# TJMakes_LiPo_Manager.net
KiCad netlist of a schematic drawn in EasyEDA Pro
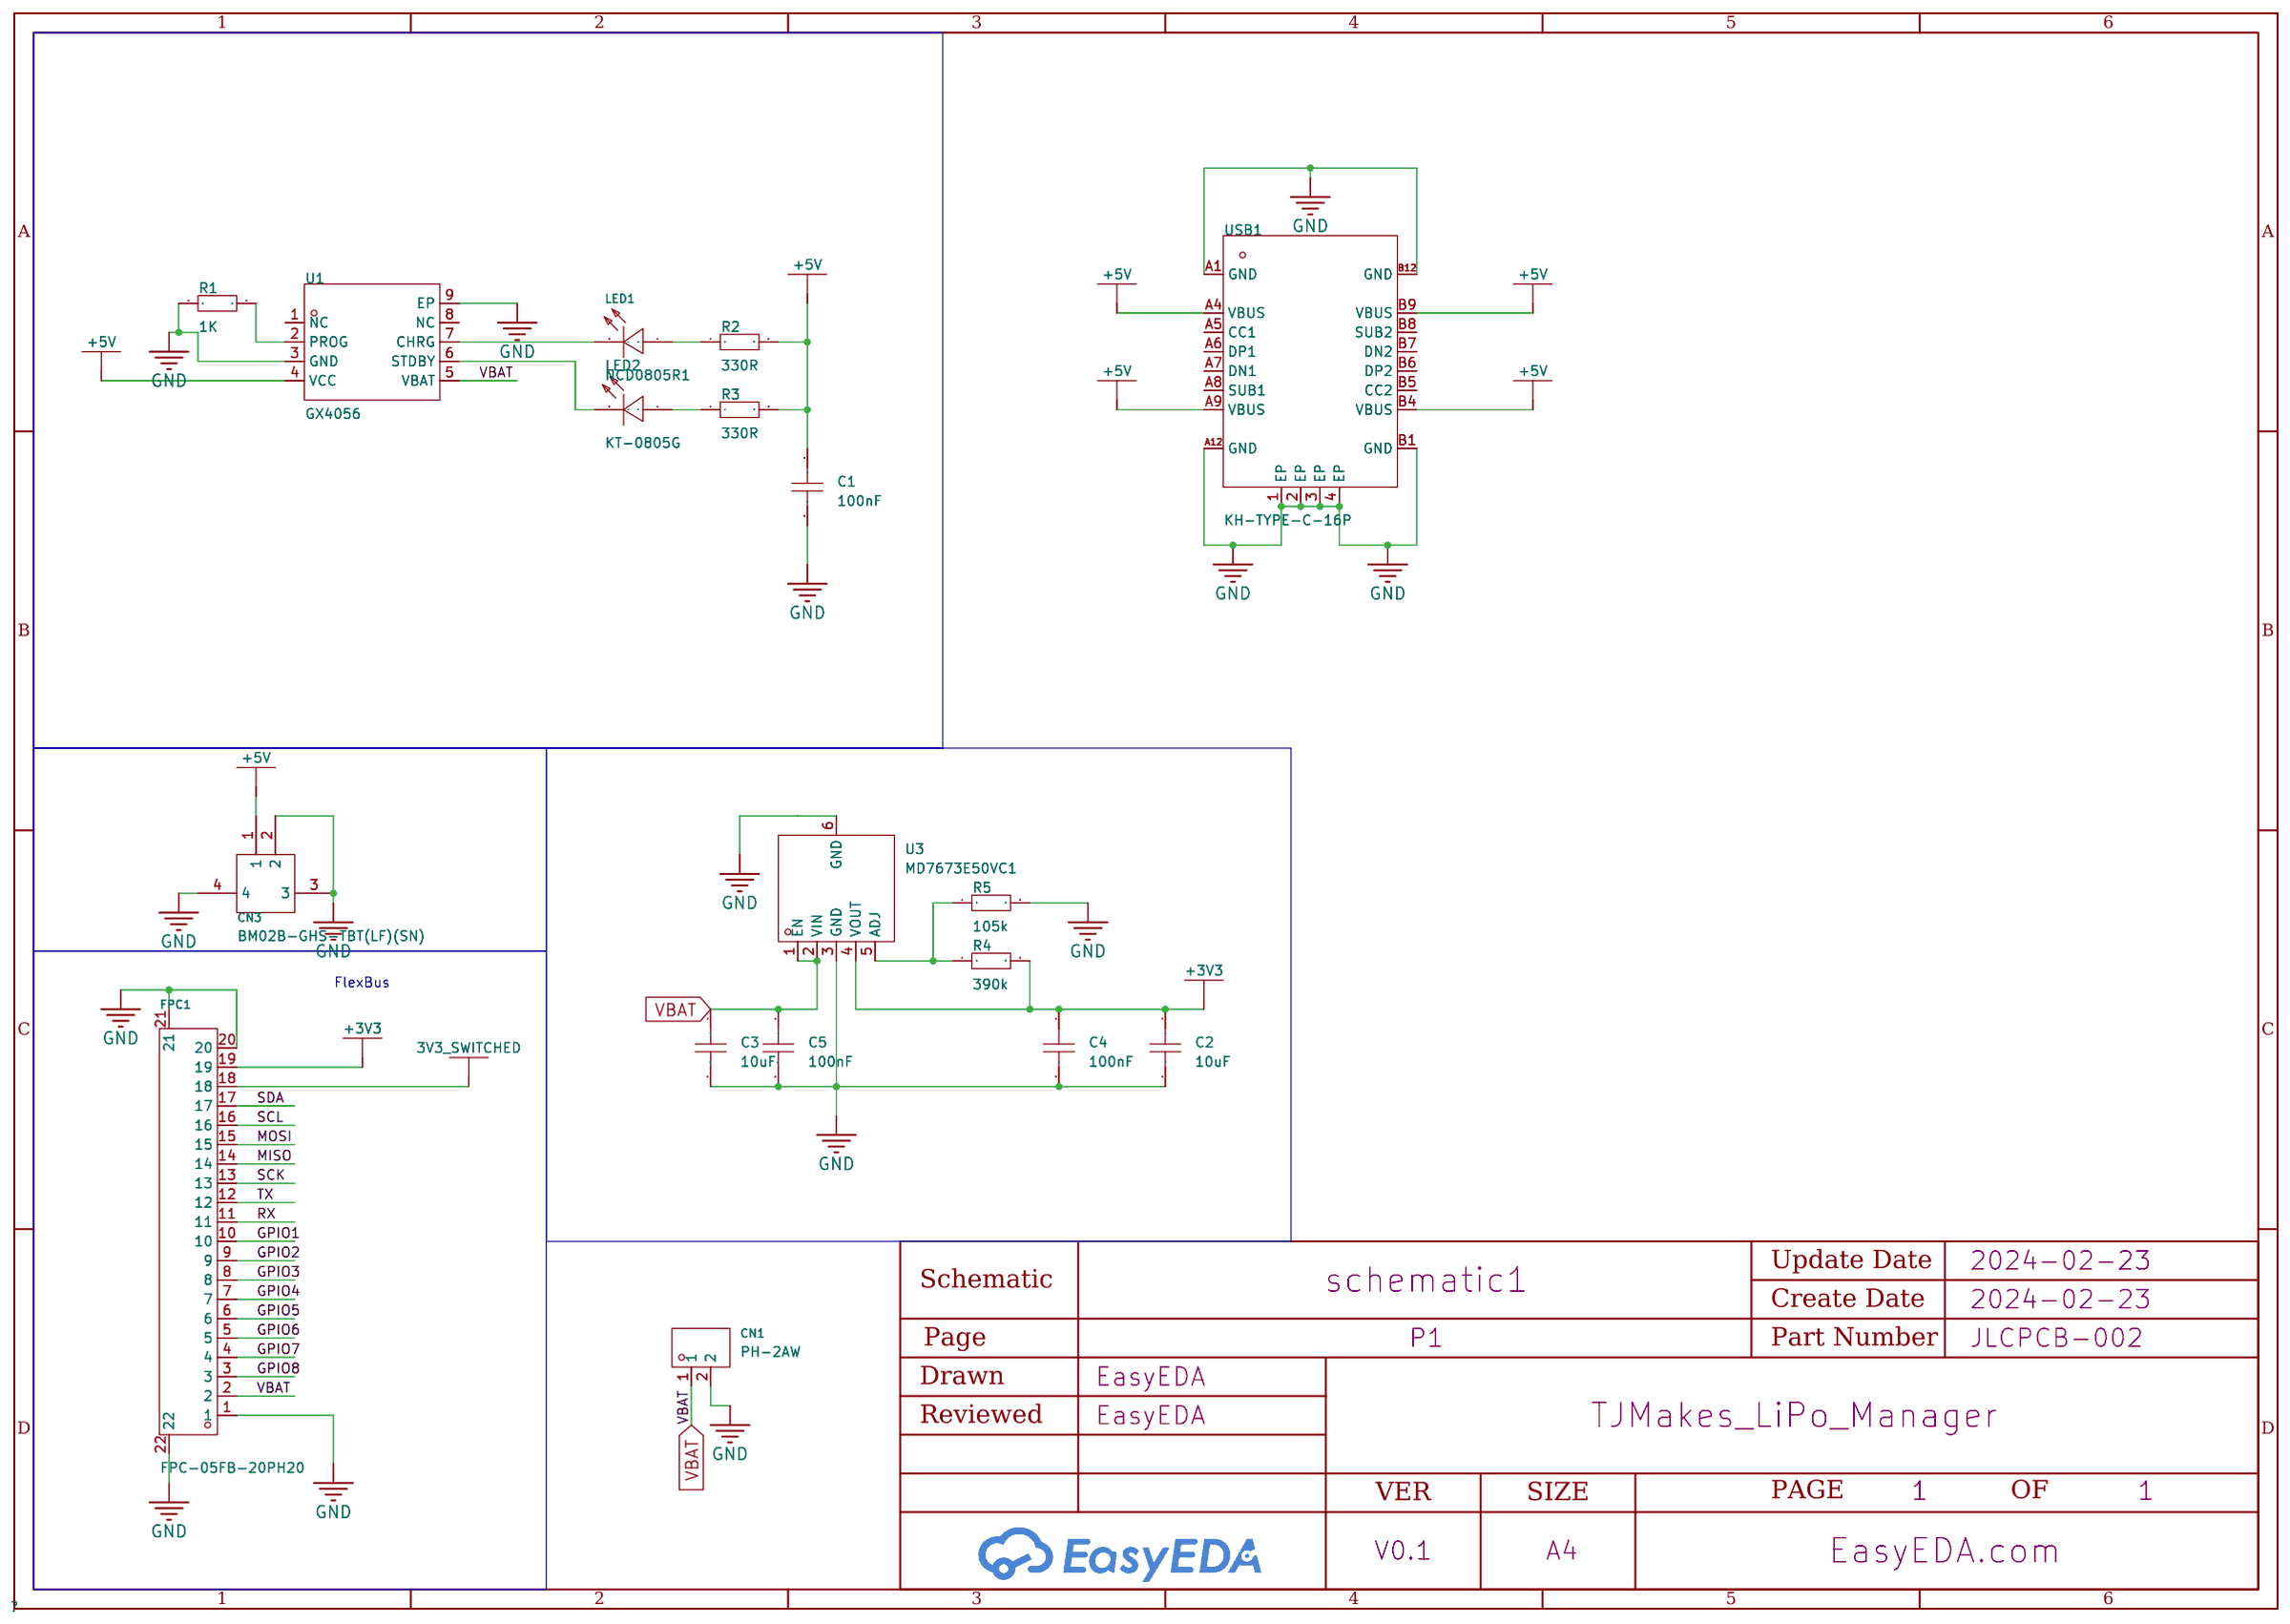
[diagram p0: schematic sheet]

(export (version "E")
  (design (tool "Eeschema 10.0.6"))
  (components
    (comp (ref "C1")
      (value "100nF")
      (footprint "easyedapro:C0603")
      (libsource (lib "easyedapro") (part "CAP"))
    )
    (comp (ref "C2")
      (value "10uF")
      (footprint "easyedapro:C0603")
      (libsource (lib "easyedapro") (part "CAP"))
    )
    (comp (ref "C3")
      (value "10uF")
      (footprint "easyedapro:C0603")
      (libsource (lib "easyedapro") (part "CAP"))
    )
    (comp (ref "C4")
      (value "100nF")
      (footprint "easyedapro:C0603")
      (libsource (lib "easyedapro") (part "CAP"))
    )
    (comp (ref "C5")
      (value "100nF")
      (footprint "easyedapro:C0603")
      (libsource (lib "easyedapro") (part "CAP"))
    )
    (comp (ref "CN1")
      (value "PH-2AW")
      (footprint "easyedapro:CONN-TH_PH-2AW")
      (fields (field (name "Manufacturer") "CAX(创都)"))
      (libsource (lib "easyedapro") (part "PH-2AW"))
    )
    (comp (ref "CN3")
      (value "BM02B-GHS-TBT(LF)(SN)")
      (footprint "easyedapro:CONN-SMD_2P-P1.25_BM02B-GHS-TBT-LF-SN")
      (fields (field (name "Manufacturer") "JST"))
      (libsource (lib "easyedapro") (part "BM02B-GHS-TBT (LF)(SN)"))
    )
    (comp (ref "FPC1")
      (value "FPC-05FB-20PH20")
      (footprint "easyedapro:FPC-SMD_20P-P0.50_FPC-05FB-20PH20")
      (fields (field (name "Manufacturer") "XUNPU(讯普)"))
      (libsource (lib "easyedapro") (part "FPC-05FB-20PH20"))
    )
    (comp (ref "LED1")
      (value "NCD0805R1")
      (footprint "easyedapro:LED0805-R-RD")
      (fields (field (name "Manufacturer") "国星光电"))
      (libsource (lib "easyedapro") (part "FC-2012HRK-620D"))
    )
    (comp (ref "LED2")
      (value "KT-0805G")
      (footprint "easyedapro:LED0805-R-RD")
      (fields (field (name "Manufacturer") "KENTO"))
      (libsource (lib "easyedapro") (part "0805G (Green)"))
    )
    (comp (ref "R1") (value "1K") (footprint "easyedapro:R0603") (libsource (lib "easyedapro") (part "Res")))
    (comp (ref "R2")
      (value "330R")
      (footprint "easyedapro:R0603")
      (libsource (lib "easyedapro") (part "Res"))
    )
    (comp (ref "R3")
      (value "330R")
      (footprint "easyedapro:R0603")
      (libsource (lib "easyedapro") (part "Res"))
    )
    (comp (ref "R4")
      (value "390k")
      (footprint "easyedapro:R0603")
      (libsource (lib "easyedapro") (part "Res"))
    )
    (comp (ref "R5")
      (value "105k")
      (footprint "easyedapro:R0603")
      (libsource (lib "easyedapro") (part "Res"))
    )
    (comp (ref "U1")
      (value "GX4056")
      (footprint "easyedapro:ESOP-8_L4.9-W3.9-P1.27-LS6.0-BL-EP")
      (description "Maximum Charge Current:1000mA")
      (fields (field (name "Manufacturer") "国芯佳品"))
      (libsource (lib "easyedapro") (part "GX4056"))
    )
    (comp (ref "U3")
      (value "MD7673E50VC1")
      (footprint "easyedapro:TO-263-5_L10.2-W8.9-P1.70-BR")
      (fields (field (name "Manufacturer") "明达微"))
      (libsource (lib "easyedapro") (part "MD7673E50VC1"))
    )
    (comp (ref "USB1")
      (value "KH-TYPE-C-16P")
      (footprint "easyedapro:USB-C-SMD_KH-TYPE-C-16P")
      (fields (field (name "Manufacturer") "kinghelm(金航标)"))
      (libsource (lib "easyedapro") (part "KH-TYPE-C-16P"))
    )
  )
  (nets
    (net (code "1") (name "+3V3") (class "Default")
      (node (ref "C2") (pin "1") (pinfunction "1_1") (pintype "input"))
      (node (ref "C4") (pin "1") (pinfunction "1_1") (pintype "input"))
      (node (ref "FPC1") (pin "19") (pinfunction "19_19") (pintype "input"))
      (node (ref "R4") (pin "2") (pinfunction "2_2") (pintype "input"))
      (node (ref "U3") (pin "4") (pinfunction "VOUT_4") (pintype "input"))
    )
    (net (code "2") (name "+5V") (class "Default")
      (node (ref "C1") (pin "1") (pinfunction "1_1") (pintype "input"))
      (node (ref "CN3") (pin "1") (pinfunction "1_1") (pintype "input"))
      (node (ref "R2") (pin "2") (pinfunction "2_2") (pintype "input"))
      (node (ref "R3") (pin "2") (pinfunction "2_2") (pintype "input"))
      (node (ref "U1") (pin "4") (pinfunction "VCC_4") (pintype "input"))
      (node (ref "USB1") (pin "A4") (pinfunction "VBUS_A4") (pintype "unspecified"))
      (node (ref "USB1") (pin "A9") (pinfunction "VBUS_A9") (pintype "unspecified"))
      (node (ref "USB1") (pin "B4") (pinfunction "VBUS_B4") (pintype "unspecified"))
      (node (ref "USB1") (pin "B9") (pinfunction "VBUS_B9") (pintype "unspecified"))
    )
    (net (code "3") (name "/GPIO1") (class "Default")
      (node (ref "FPC1") (pin "10") (pinfunction "10_10") (pintype "input"))
    )
    (net (code "4") (name "/GPIO2") (class "Default")
      (node (ref "FPC1") (pin "9") (pinfunction "9_9") (pintype "input"))
    )
    (net (code "5") (name "/GPIO3") (class "Default")
      (node (ref "FPC1") (pin "8") (pinfunction "8_8") (pintype "input"))
    )
    (net (code "6") (name "/GPIO4") (class "Default")
      (node (ref "FPC1") (pin "7") (pinfunction "7_7") (pintype "input"))
    )
    (net (code "7") (name "/GPIO5") (class "Default")
      (node (ref "FPC1") (pin "6") (pinfunction "6_6") (pintype "input"))
    )
    (net (code "8") (name "/GPIO6") (class "Default")
      (node (ref "FPC1") (pin "5") (pinfunction "5_5") (pintype "input"))
    )
    (net (code "9") (name "/GPIO7") (class "Default")
      (node (ref "FPC1") (pin "4") (pinfunction "4_4") (pintype "input"))
    )
    (net (code "10") (name "/GPIO8") (class "Default")
      (node (ref "FPC1") (pin "3") (pinfunction "3_3") (pintype "input"))
    )
    (net (code "11") (name "/MISO") (class "Default")
      (node (ref "FPC1") (pin "14") (pinfunction "14_14") (pintype "input"))
    )
    (net (code "12") (name "/MOSI") (class "Default")
      (node (ref "FPC1") (pin "15") (pinfunction "15_15") (pintype "input"))
    )
    (net (code "13") (name "/RX") (class "Default")
      (node (ref "FPC1") (pin "11") (pinfunction "11_11") (pintype "input"))
    )
    (net (code "14") (name "/SCK") (class "Default")
      (node (ref "FPC1") (pin "13") (pinfunction "13_13") (pintype "input"))
    )
    (net (code "15") (name "/SCL") (class "Default")
      (node (ref "FPC1") (pin "16") (pinfunction "16_16") (pintype "input"))
    )
    (net (code "16") (name "/SDA") (class "Default")
      (node (ref "FPC1") (pin "17") (pinfunction "17_17") (pintype "input"))
    )
    (net (code "17") (name "/TX") (class "Default")
      (node (ref "FPC1") (pin "12") (pinfunction "12_12") (pintype "input"))
    )
    (net (code "18") (name "3V3_SWITCHED") (class "Default")
      (node (ref "FPC1") (pin "18") (pinfunction "18_18") (pintype "input"))
    )
    (net (code "19") (name "GND") (class "Default")
      (node (ref "C1") (pin "2") (pinfunction "2_2") (pintype "input"))
      (node (ref "C2") (pin "2") (pinfunction "2_2") (pintype "input"))
      (node (ref "C3") (pin "2") (pinfunction "2_2") (pintype "input"))
      (node (ref "C4") (pin "2") (pinfunction "2_2") (pintype "input"))
      (node (ref "C5") (pin "2") (pinfunction "2_2") (pintype "input"))
      (node (ref "CN1") (pin "2") (pinfunction "2_2") (pintype "input"))
      (node (ref "CN3") (pin "2") (pinfunction "2_2") (pintype "input"))
      (node (ref "CN3") (pin "3") (pinfunction "3_3") (pintype "input"))
      (node (ref "CN3") (pin "4") (pinfunction "4_4") (pintype "input"))
      (node (ref "FPC1") (pin "1") (pinfunction "1_1") (pintype "input"))
      (node (ref "FPC1") (pin "20") (pinfunction "20_20") (pintype "input"))
      (node (ref "FPC1") (pin "21") (pinfunction "21_21") (pintype "input"))
      (node (ref "FPC1") (pin "22") (pinfunction "22_22") (pintype "input"))
      (node (ref "R1") (pin "1") (pinfunction "1_1") (pintype "input"))
      (node (ref "R5") (pin "2") (pinfunction "2_2") (pintype "input"))
      (node (ref "U1") (pin "3") (pinfunction "GND_3") (pintype "input"))
      (node (ref "U1") (pin "9") (pinfunction "EP_9") (pintype "input"))
      (node (ref "U3") (pin "3") (pinfunction "GND_3") (pintype "input"))
      (node (ref "U3") (pin "6") (pinfunction "GND_6") (pintype "input"))
      (node (ref "USB1") (pin "1") (pinfunction "EP_1") (pintype "unspecified"))
      (node (ref "USB1") (pin "2") (pinfunction "EP_2") (pintype "unspecified"))
      (node (ref "USB1") (pin "3") (pinfunction "EP_3") (pintype "unspecified"))
      (node (ref "USB1") (pin "4") (pinfunction "EP_4") (pintype "unspecified"))
      (node (ref "USB1") (pin "A1") (pinfunction "GND_A1") (pintype "unspecified"))
      (node (ref "USB1") (pin "A12") (pinfunction "GND_A12") (pintype "unspecified"))
      (node (ref "USB1") (pin "B1") (pinfunction "GND_B1") (pintype "unspecified"))
      (node (ref "USB1") (pin "B12") (pinfunction "GND_B12") (pintype "unspecified"))
    )
    (net (code "20") (name "Net-(LED1-+)") (class "Default")
      (node (ref "LED1") (pin "1") (pinfunction "+_1") (pintype "input"))
      (node (ref "R2") (pin "1") (pinfunction "1_1") (pintype "input"))
    )
    (net (code "21") (name "Net-(LED1--)") (class "Default")
      (node (ref "LED1") (pin "2") (pinfunction "-_2") (pintype "input"))
      (node (ref "U1") (pin "7") (pinfunction "CHRG_7") (pintype "input"))
    )
    (net (code "22") (name "Net-(LED2-A)") (class "Default")
      (node (ref "LED2") (pin "1") (pinfunction "A_1") (pintype "unspecified"))
      (node (ref "R3") (pin "1") (pinfunction "1_1") (pintype "input"))
    )
    (net (code "23") (name "Net-(LED2-K)") (class "Default")
      (node (ref "LED2") (pin "2") (pinfunction "K_2") (pintype "unspecified"))
      (node (ref "U1") (pin "6") (pinfunction "STDBY_6") (pintype "input"))
    )
    (net (code "24") (name "Net-(U1-PROG)") (class "Default")
      (node (ref "R1") (pin "2") (pinfunction "2_2") (pintype "input"))
      (node (ref "U1") (pin "2") (pinfunction "PROG_2") (pintype "input"))
    )
    (net (code "25") (name "Net-(U3-ADJ)") (class "Default")
      (node (ref "R4") (pin "1") (pinfunction "1_1") (pintype "input"))
      (node (ref "R5") (pin "1") (pinfunction "1_1") (pintype "input"))
      (node (ref "U3") (pin "5") (pinfunction "ADJ_5") (pintype "input"))
    )
    (net (code "26") (name "VBAT") (class "Default")
      (node (ref "C3") (pin "1") (pinfunction "1_1") (pintype "input"))
      (node (ref "C5") (pin "1") (pinfunction "1_1") (pintype "input"))
      (node (ref "CN1") (pin "1") (pinfunction "1_1") (pintype "input"))
      (node (ref "FPC1") (pin "2") (pinfunction "2_2") (pintype "input"))
      (node (ref "U1") (pin "5") (pinfunction "VBAT_5") (pintype "input"))
      (node (ref "U3") (pin "1") (pinfunction "EN_1") (pintype "input"))
      (node (ref "U3") (pin "2") (pinfunction "VIN_2") (pintype "input"))
    )
    (net (code "27") (name "unconnected-(U1-NC-Pad1)") (class "Default")
      (node (ref "U1") (pin "1") (pinfunction "NC_1") (pintype "input"))
    )
    (net (code "28") (name "unconnected-(U1-NC-Pad8)") (class "Default")
      (node (ref "U1") (pin "8") (pinfunction "NC_8") (pintype "input"))
    )
    (net (code "29") (name "unconnected-(USB1-CC1-PadA5)") (class "Default")
      (node (ref "USB1") (pin "A5") (pinfunction "CC1_A5") (pintype "unspecified"))
    )
    (net (code "30") (name "unconnected-(USB1-CC2-PadB5)") (class "Default")
      (node (ref "USB1") (pin "B5") (pinfunction "CC2_B5") (pintype "unspecified"))
    )
    (net (code "31") (name "unconnected-(USB1-DN1-PadA7)") (class "Default")
      (node (ref "USB1") (pin "A7") (pinfunction "DN1_A7") (pintype "unspecified"))
    )
    (net (code "32") (name "unconnected-(USB1-DN2-PadB7)") (class "Default")
      (node (ref "USB1") (pin "B7") (pinfunction "DN2_B7") (pintype "unspecified"))
    )
    (net (code "33") (name "unconnected-(USB1-DP1-PadA6)") (class "Default")
      (node (ref "USB1") (pin "A6") (pinfunction "DP1_A6") (pintype "unspecified"))
    )
    (net (code "34") (name "unconnected-(USB1-DP2-PadB6)") (class "Default")
      (node (ref "USB1") (pin "B6") (pinfunction "DP2_B6") (pintype "unspecified"))
    )
    (net (code "35") (name "unconnected-(USB1-SUB1-PadA8)") (class "Default")
      (node (ref "USB1") (pin "A8") (pinfunction "SUB1_A8") (pintype "unspecified"))
    )
    (net (code "36") (name "unconnected-(USB1-SUB2-PadB8)") (class "Default")
      (node (ref "USB1") (pin "B8") (pinfunction "SUB2_B8") (pintype "unspecified"))
    )
  )
)
